# spi_v4.net
KiCad netlist of a schematic drawn in EAGLE
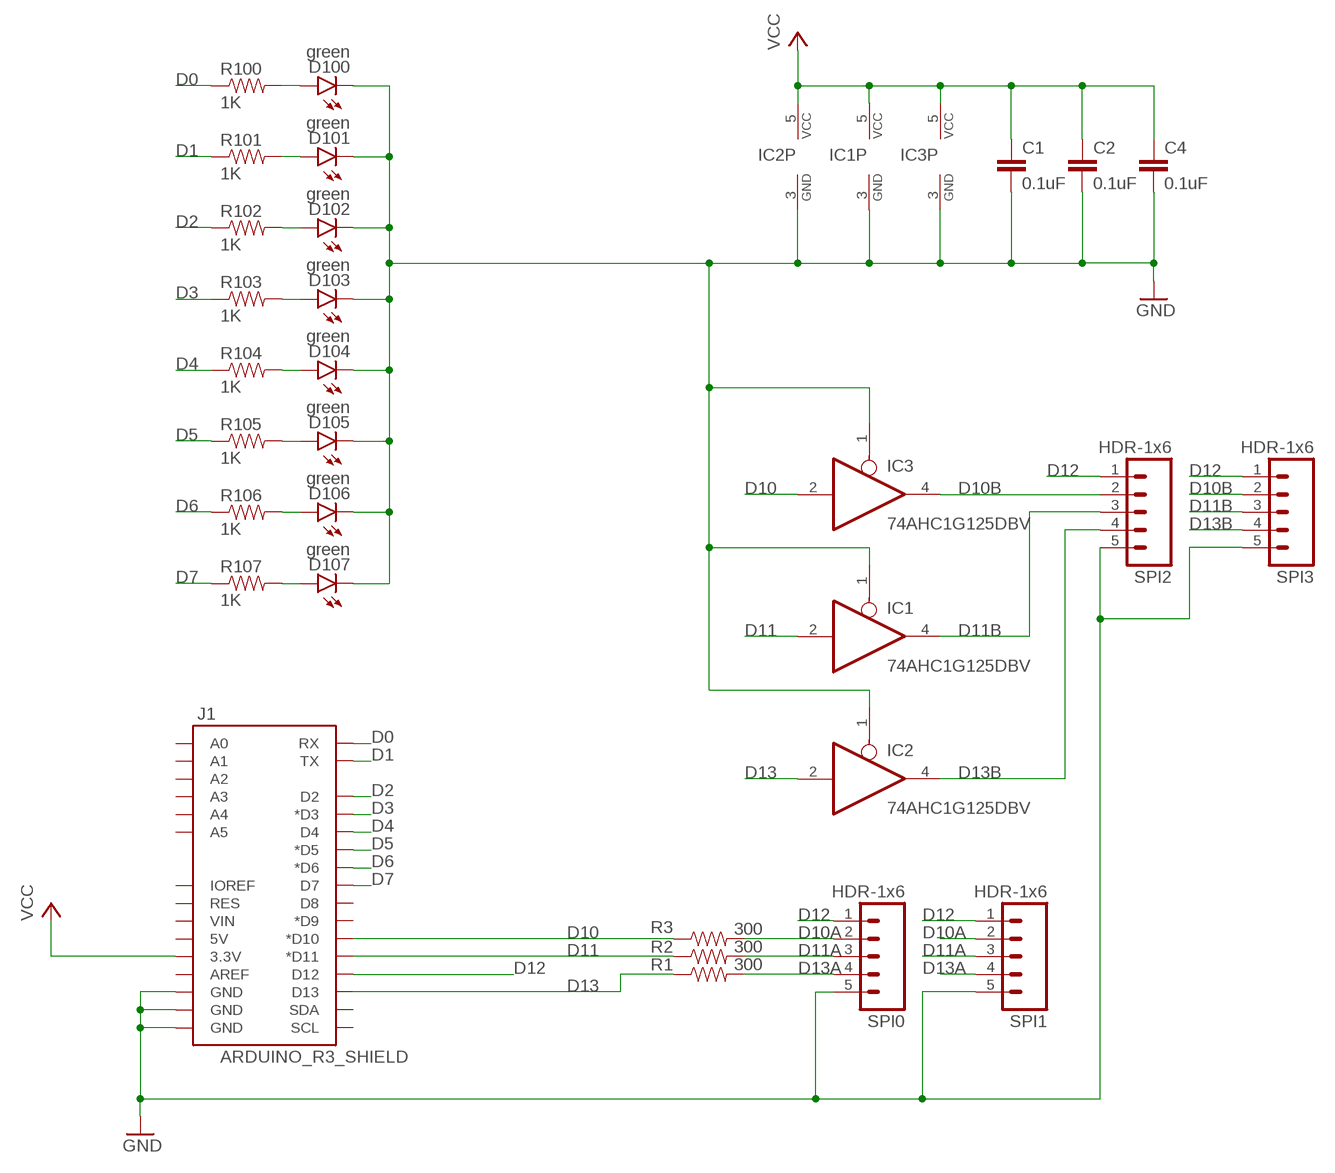
[diagram p0: schematic, sheet 1]

(export (version "E")
  (design (tool "Eeschema 10.0.6"))
  (components
    (comp (ref "C1")
      (value "0.1uF")
      (footprint "eagle-import:0805-CAP")
      (fields (field (name "PROD_ID") "0805"))
      (libsource (lib "eagle-import") (part "1.0UF-25V-+80/-20(0805){dblquote}"))
    )
    (comp (ref "C2")
      (value "0.1uF")
      (footprint "eagle-import:0805-CAP")
      (fields (field (name "PROD_ID") "0805"))
      (libsource (lib "eagle-import") (part "1.0UF-25V-+80/-20(0805){dblquote}"))
    )
    (comp (ref "C4")
      (value "0.1uF")
      (footprint "eagle-import:0805-CAP")
      (fields (field (name "PROD_ID") "0805"))
      (libsource (lib "eagle-import") (part "1.0UF-25V-+80/-20(0805){dblquote}"))
    )
    (comp (ref "D100")
      (value "green")
      (footprint "eagle-import:FKIT-LED-1206")
      (libsource (lib "eagle-import") (part "LED-FKIT-1206"))
    )
    (comp (ref "D101")
      (value "green")
      (footprint "eagle-import:FKIT-LED-1206")
      (libsource (lib "eagle-import") (part "LED-FKIT-1206"))
    )
    (comp (ref "D102")
      (value "green")
      (footprint "eagle-import:FKIT-LED-1206")
      (libsource (lib "eagle-import") (part "LED-FKIT-1206"))
    )
    (comp (ref "D103")
      (value "green")
      (footprint "eagle-import:FKIT-LED-1206")
      (libsource (lib "eagle-import") (part "LED-FKIT-1206"))
    )
    (comp (ref "D104")
      (value "green")
      (footprint "eagle-import:FKIT-LED-1206")
      (libsource (lib "eagle-import") (part "LED-FKIT-1206"))
    )
    (comp (ref "D105")
      (value "green")
      (footprint "eagle-import:FKIT-LED-1206")
      (libsource (lib "eagle-import") (part "LED-FKIT-1206"))
    )
    (comp (ref "D106")
      (value "green")
      (footprint "eagle-import:FKIT-LED-1206")
      (libsource (lib "eagle-import") (part "LED-FKIT-1206"))
    )
    (comp (ref "D107")
      (value "green")
      (footprint "eagle-import:FKIT-LED-1206")
      (libsource (lib "eagle-import") (part "LED-FKIT-1206"))
    )
    (comp (ref "IC1")
      (value "74AHC1G125DBV")
      (footprint "eagle-import:SOT23-5")
      (libsource (lib "eagle-import") (part "741G125DBVAHC"))
    )
    (comp (ref "IC2")
      (value "74AHC1G125DBV")
      (footprint "eagle-import:SOT23-5")
      (libsource (lib "eagle-import") (part "741G125DBVAHC"))
    )
    (comp (ref "IC3")
      (value "74AHC1G125DBV")
      (footprint "eagle-import:SOT23-5")
      (libsource (lib "eagle-import") (part "741G125DBVAHC"))
    )
    (comp (ref "J1")
      (value "ARDUINO_R3_SHIELD")
      (footprint "eagle-import:UNO_R3_SHIELD")
      (libsource (lib "eagle-import") (part "ARDUINO_R3_SHIELD"))
    )
    (comp (ref "R1")
      (value "300")
      (footprint "eagle-import:AXIAL-0.4")
      (libsource (lib "eagle-import") (part "RESISTORPTH-1/4W"))
    )
    (comp (ref "R2")
      (value "300")
      (footprint "eagle-import:AXIAL-0.4")
      (libsource (lib "eagle-import") (part "RESISTORPTH-1/4W"))
    )
    (comp (ref "R3")
      (value "300")
      (footprint "eagle-import:AXIAL-0.4")
      (libsource (lib "eagle-import") (part "RESISTORPTH-1/4W"))
    )
    (comp (ref "R100")
      (value "1K")
      (footprint "eagle-import:0805")
      (libsource (lib "eagle-import") (part "RESISTOR0805-RES"))
    )
    (comp (ref "R101")
      (value "1K")
      (footprint "eagle-import:0805")
      (libsource (lib "eagle-import") (part "RESISTOR0805-RES"))
    )
    (comp (ref "R102")
      (value "1K")
      (footprint "eagle-import:0805")
      (libsource (lib "eagle-import") (part "RESISTOR0805-RES"))
    )
    (comp (ref "R103")
      (value "1K")
      (footprint "eagle-import:0805")
      (libsource (lib "eagle-import") (part "RESISTOR0805-RES"))
    )
    (comp (ref "R104")
      (value "1K")
      (footprint "eagle-import:0805")
      (libsource (lib "eagle-import") (part "RESISTOR0805-RES"))
    )
    (comp (ref "R105")
      (value "1K")
      (footprint "eagle-import:0805")
      (libsource (lib "eagle-import") (part "RESISTOR0805-RES"))
    )
    (comp (ref "R106")
      (value "1K")
      (footprint "eagle-import:0805")
      (libsource (lib "eagle-import") (part "RESISTOR0805-RES"))
    )
    (comp (ref "R107")
      (value "1K")
      (footprint "eagle-import:0805")
      (libsource (lib "eagle-import") (part "RESISTOR0805-RES"))
    )
    (comp (ref "SPI0")
      (value "HDR-1x6")
      (footprint "eagle-import:1X05_LONGPADS")
      (libsource (lib "eagle-import") (part "M05PTH_LONGPADS"))
    )
    (comp (ref "SPI1")
      (value "HDR-1x6")
      (footprint "eagle-import:1X05_LONGPADS")
      (libsource (lib "eagle-import") (part "M05PTH_LONGPADS"))
    )
    (comp (ref "SPI2")
      (value "HDR-1x6")
      (footprint "eagle-import:1X05_LONGPADS")
      (libsource (lib "eagle-import") (part "M05PTH_LONGPADS"))
    )
    (comp (ref "SPI3")
      (value "HDR-1x6")
      (footprint "eagle-import:1X05_LONGPADS")
      (libsource (lib "eagle-import") (part "M05PTH_LONGPADS"))
    )
  )
  (nets
    (net (code "1") (name "/D0") (class "Default")
      (node (ref "J1") (pin "RX") (pinfunction "RX_RX") (pintype "bidirectional"))
      (node (ref "R100") (pin "1") (pinfunction "1_1") (pintype "passive"))
    )
    (net (code "2") (name "/D1") (class "Default")
      (node (ref "J1") (pin "TX") (pinfunction "TX_TX") (pintype "bidirectional"))
      (node (ref "R101") (pin "1") (pinfunction "1_1") (pintype "passive"))
    )
    (net (code "3") (name "/D2") (class "Default")
      (node (ref "J1") (pin "D2") (pinfunction "D2_D2") (pintype "bidirectional"))
      (node (ref "R102") (pin "1") (pinfunction "1_1") (pintype "passive"))
    )
    (net (code "4") (name "/D3") (class "Default")
      (node (ref "J1") (pin "D3") (pinfunction "*D3_D3") (pintype "bidirectional"))
      (node (ref "R103") (pin "1") (pinfunction "1_1") (pintype "passive"))
    )
    (net (code "5") (name "/D4") (class "Default")
      (node (ref "J1") (pin "D4") (pinfunction "D4_D4") (pintype "bidirectional"))
      (node (ref "R104") (pin "1") (pinfunction "1_1") (pintype "passive"))
    )
    (net (code "6") (name "/D5") (class "Default")
      (node (ref "J1") (pin "D5") (pinfunction "*D5_D5") (pintype "bidirectional"))
      (node (ref "R105") (pin "1") (pinfunction "1_1") (pintype "passive"))
    )
    (net (code "7") (name "/D6") (class "Default")
      (node (ref "J1") (pin "D6") (pinfunction "*D6_D6") (pintype "bidirectional"))
      (node (ref "R106") (pin "1") (pinfunction "1_1") (pintype "passive"))
    )
    (net (code "8") (name "/D7") (class "Default")
      (node (ref "J1") (pin "D7") (pinfunction "D7_D7") (pintype "bidirectional"))
      (node (ref "R107") (pin "1") (pinfunction "1_1") (pintype "passive"))
    )
    (net (code "9") (name "/D10") (class "Default")
      (node (ref "IC3") (pin "2") (pinfunction "I_2") (pintype "input"))
      (node (ref "J1") (pin "D10") (pinfunction "*D10_D10") (pintype "bidirectional"))
      (node (ref "R3") (pin "P$1") (pinfunction "1_P$1") (pintype "passive"))
    )
    (net (code "10") (name "/D10A") (class "Default")
      (node (ref "R3") (pin "P$2") (pinfunction "2_P$2") (pintype "passive"))
      (node (ref "SPI0") (pin "2") (pinfunction "2_2") (pintype "passive"))
      (node (ref "SPI1") (pin "2") (pinfunction "2_2") (pintype "passive"))
    )
    (net (code "11") (name "/D10B") (class "Default")
      (node (ref "IC3") (pin "4") (pinfunction "O_4") (pintype "tri_state"))
      (node (ref "SPI2") (pin "2") (pinfunction "2_2") (pintype "passive"))
      (node (ref "SPI3") (pin "2") (pinfunction "2_2") (pintype "passive"))
    )
    (net (code "12") (name "/D11") (class "Default")
      (node (ref "IC1") (pin "2") (pinfunction "I_2") (pintype "input"))
      (node (ref "J1") (pin "D11") (pinfunction "*D11_D11") (pintype "bidirectional"))
      (node (ref "R2") (pin "P$1") (pinfunction "1_P$1") (pintype "passive"))
    )
    (net (code "13") (name "/D11A") (class "Default")
      (node (ref "R2") (pin "P$2") (pinfunction "2_P$2") (pintype "passive"))
      (node (ref "SPI0") (pin "3") (pinfunction "3_3") (pintype "passive"))
      (node (ref "SPI1") (pin "3") (pinfunction "3_3") (pintype "passive"))
    )
    (net (code "14") (name "/D11B") (class "Default")
      (node (ref "IC1") (pin "4") (pinfunction "O_4") (pintype "tri_state"))
      (node (ref "SPI2") (pin "3") (pinfunction "3_3") (pintype "passive"))
      (node (ref "SPI3") (pin "3") (pinfunction "3_3") (pintype "passive"))
    )
    (net (code "15") (name "/D12") (class "Default")
      (node (ref "J1") (pin "D12") (pinfunction "D12_D12") (pintype "bidirectional"))
      (node (ref "SPI0") (pin "1") (pinfunction "1_1") (pintype "passive"))
      (node (ref "SPI1") (pin "1") (pinfunction "1_1") (pintype "passive"))
      (node (ref "SPI2") (pin "1") (pinfunction "1_1") (pintype "passive"))
      (node (ref "SPI3") (pin "1") (pinfunction "1_1") (pintype "passive"))
    )
    (net (code "16") (name "/D13") (class "Default")
      (node (ref "IC2") (pin "2") (pinfunction "I_2") (pintype "input"))
      (node (ref "J1") (pin "D13") (pinfunction "D13_D13") (pintype "bidirectional"))
      (node (ref "R1") (pin "P$1") (pinfunction "1_P$1") (pintype "passive"))
    )
    (net (code "17") (name "/D13A") (class "Default")
      (node (ref "R1") (pin "P$2") (pinfunction "2_P$2") (pintype "passive"))
      (node (ref "SPI0") (pin "4") (pinfunction "4_4") (pintype "passive"))
      (node (ref "SPI1") (pin "4") (pinfunction "4_4") (pintype "passive"))
    )
    (net (code "18") (name "/D13B") (class "Default")
      (node (ref "IC2") (pin "4") (pinfunction "O_4") (pintype "tri_state"))
      (node (ref "SPI2") (pin "4") (pinfunction "4_4") (pintype "passive"))
      (node (ref "SPI3") (pin "4") (pinfunction "4_4") (pintype "passive"))
    )
    (net (code "19") (name "GND") (class "Default")
      (node (ref "C1") (pin "2") (pinfunction "2_2") (pintype "passive"))
      (node (ref "C2") (pin "2") (pinfunction "2_2") (pintype "passive"))
      (node (ref "C4") (pin "2") (pinfunction "2_2") (pintype "passive"))
      (node (ref "D100") (pin "C") (pinfunction "C_C") (pintype "passive"))
      (node (ref "D101") (pin "C") (pinfunction "C_C") (pintype "passive"))
      (node (ref "D102") (pin "C") (pinfunction "C_C") (pintype "passive"))
      (node (ref "D103") (pin "C") (pinfunction "C_C") (pintype "passive"))
      (node (ref "D104") (pin "C") (pinfunction "C_C") (pintype "passive"))
      (node (ref "D105") (pin "C") (pinfunction "C_C") (pintype "passive"))
      (node (ref "D106") (pin "C") (pinfunction "C_C") (pintype "passive"))
      (node (ref "D107") (pin "C") (pinfunction "C_C") (pintype "passive"))
      (node (ref "IC1") (pin "1") (pinfunction "OE_1") (pintype "input"))
      (node (ref "IC1") (pin "3") (pinfunction "GND_3") (pintype "power_in"))
      (node (ref "IC2") (pin "1") (pinfunction "OE_1") (pintype "input"))
      (node (ref "IC2") (pin "3") (pinfunction "GND_3") (pintype "power_in"))
      (node (ref "IC3") (pin "1") (pinfunction "OE_1") (pintype "input"))
      (node (ref "IC3") (pin "3") (pinfunction "GND_3") (pintype "power_in"))
      (node (ref "J1") (pin "GND@0") (pinfunction "GND_GND@0") (pintype "bidirectional"))
      (node (ref "J1") (pin "GND@1") (pinfunction "GND_GND@1") (pintype "bidirectional"))
      (node (ref "J1") (pin "GND@2") (pinfunction "GND_GND@2") (pintype "bidirectional"))
      (node (ref "SPI0") (pin "5") (pinfunction "5_5") (pintype "passive"))
      (node (ref "SPI1") (pin "5") (pinfunction "5_5") (pintype "passive"))
      (node (ref "SPI2") (pin "5") (pinfunction "5_5") (pintype "passive"))
      (node (ref "SPI3") (pin "5") (pinfunction "5_5") (pintype "passive"))
    )
    (net (code "20") (name "Net-(D100-PadA)") (class "Default")
      (node (ref "D100") (pin "A") (pinfunction "A_A") (pintype "passive"))
      (node (ref "R100") (pin "2") (pinfunction "2_2") (pintype "passive"))
    )
    (net (code "21") (name "Net-(D101-PadA)") (class "Default")
      (node (ref "D101") (pin "A") (pinfunction "A_A") (pintype "passive"))
      (node (ref "R101") (pin "2") (pinfunction "2_2") (pintype "passive"))
    )
    (net (code "22") (name "Net-(D102-PadA)") (class "Default")
      (node (ref "D102") (pin "A") (pinfunction "A_A") (pintype "passive"))
      (node (ref "R102") (pin "2") (pinfunction "2_2") (pintype "passive"))
    )
    (net (code "23") (name "Net-(D103-PadA)") (class "Default")
      (node (ref "D103") (pin "A") (pinfunction "A_A") (pintype "passive"))
      (node (ref "R103") (pin "2") (pinfunction "2_2") (pintype "passive"))
    )
    (net (code "24") (name "Net-(D104-PadA)") (class "Default")
      (node (ref "D104") (pin "A") (pinfunction "A_A") (pintype "passive"))
      (node (ref "R104") (pin "2") (pinfunction "2_2") (pintype "passive"))
    )
    (net (code "25") (name "Net-(D105-PadA)") (class "Default")
      (node (ref "D105") (pin "A") (pinfunction "A_A") (pintype "passive"))
      (node (ref "R105") (pin "2") (pinfunction "2_2") (pintype "passive"))
    )
    (net (code "26") (name "Net-(D106-PadA)") (class "Default")
      (node (ref "D106") (pin "A") (pinfunction "A_A") (pintype "passive"))
      (node (ref "R106") (pin "2") (pinfunction "2_2") (pintype "passive"))
    )
    (net (code "27") (name "Net-(D107-PadA)") (class "Default")
      (node (ref "D107") (pin "A") (pinfunction "A_A") (pintype "passive"))
      (node (ref "R107") (pin "2") (pinfunction "2_2") (pintype "passive"))
    )
    (net (code "28") (name "VCC") (class "Default")
      (node (ref "C1") (pin "1") (pinfunction "1_1") (pintype "passive"))
      (node (ref "C2") (pin "1") (pinfunction "1_1") (pintype "passive"))
      (node (ref "C4") (pin "1") (pinfunction "1_1") (pintype "passive"))
      (node (ref "IC1") (pin "5") (pinfunction "VCC_5") (pintype "power_in"))
      (node (ref "IC2") (pin "5") (pinfunction "VCC_5") (pintype "power_in"))
      (node (ref "IC3") (pin "5") (pinfunction "VCC_5") (pintype "power_in"))
      (node (ref "J1") (pin "3.3V") (pinfunction "3.3V_3.3V") (pintype "bidirectional"))
    )
    (net (code "29") (name "unconnected-(J1-*D9-PadD9)") (class "Default")
      (node (ref "J1") (pin "D9") (pinfunction "*D9_D9") (pintype "bidirectional"))
    )
    (net (code "30") (name "unconnected-(J1-Pad5V)") (class "Default")
      (node (ref "J1") (pin "5V") (pinfunction "5V_5V") (pintype "bidirectional"))
    )
    (net (code "31") (name "unconnected-(J1-PadA0)") (class "Default")
      (node (ref "J1") (pin "A0") (pinfunction "A0_A0") (pintype "bidirectional"))
    )
    (net (code "32") (name "unconnected-(J1-PadA1)") (class "Default")
      (node (ref "J1") (pin "A1") (pinfunction "A1_A1") (pintype "bidirectional"))
    )
    (net (code "33") (name "unconnected-(J1-PadA2)") (class "Default")
      (node (ref "J1") (pin "A2") (pinfunction "A2_A2") (pintype "bidirectional"))
    )
    (net (code "34") (name "unconnected-(J1-PadA3)") (class "Default")
      (node (ref "J1") (pin "A3") (pinfunction "A3_A3") (pintype "bidirectional"))
    )
    (net (code "35") (name "unconnected-(J1-PadA4)") (class "Default")
      (node (ref "J1") (pin "A4") (pinfunction "A4_A4") (pintype "bidirectional"))
    )
    (net (code "36") (name "unconnected-(J1-PadA5)") (class "Default")
      (node (ref "J1") (pin "A5") (pinfunction "A5_A5") (pintype "bidirectional"))
    )
    (net (code "37") (name "unconnected-(J1-PadAREF)") (class "Default")
      (node (ref "J1") (pin "AREF") (pinfunction "AREF_AREF") (pintype "bidirectional"))
    )
    (net (code "38") (name "unconnected-(J1-PadD8)") (class "Default")
      (node (ref "J1") (pin "D8") (pinfunction "D8_D8") (pintype "bidirectional"))
    )
    (net (code "39") (name "unconnected-(J1-PadIOREF)") (class "Default")
      (node (ref "J1") (pin "IOREF") (pinfunction "IOREF_IOREF") (pintype "bidirectional"))
    )
    (net (code "40") (name "unconnected-(J1-PadRES)") (class "Default")
      (node (ref "J1") (pin "RES") (pinfunction "RES_RES") (pintype "bidirectional"))
    )
    (net (code "41") (name "unconnected-(J1-PadSCL)") (class "Default")
      (node (ref "J1") (pin "SCL") (pinfunction "SCL_SCL") (pintype "bidirectional"))
    )
    (net (code "42") (name "unconnected-(J1-PadSDA)") (class "Default")
      (node (ref "J1") (pin "SDA") (pinfunction "SDA_SDA") (pintype "bidirectional"))
    )
    (net (code "43") (name "unconnected-(J1-PadVIN)") (class "Default")
      (node (ref "J1") (pin "VIN") (pinfunction "VIN_VIN") (pintype "bidirectional"))
    )
  )
)
